# schematic.net
KiCad netlist of a schematic drawn in Altium Designer
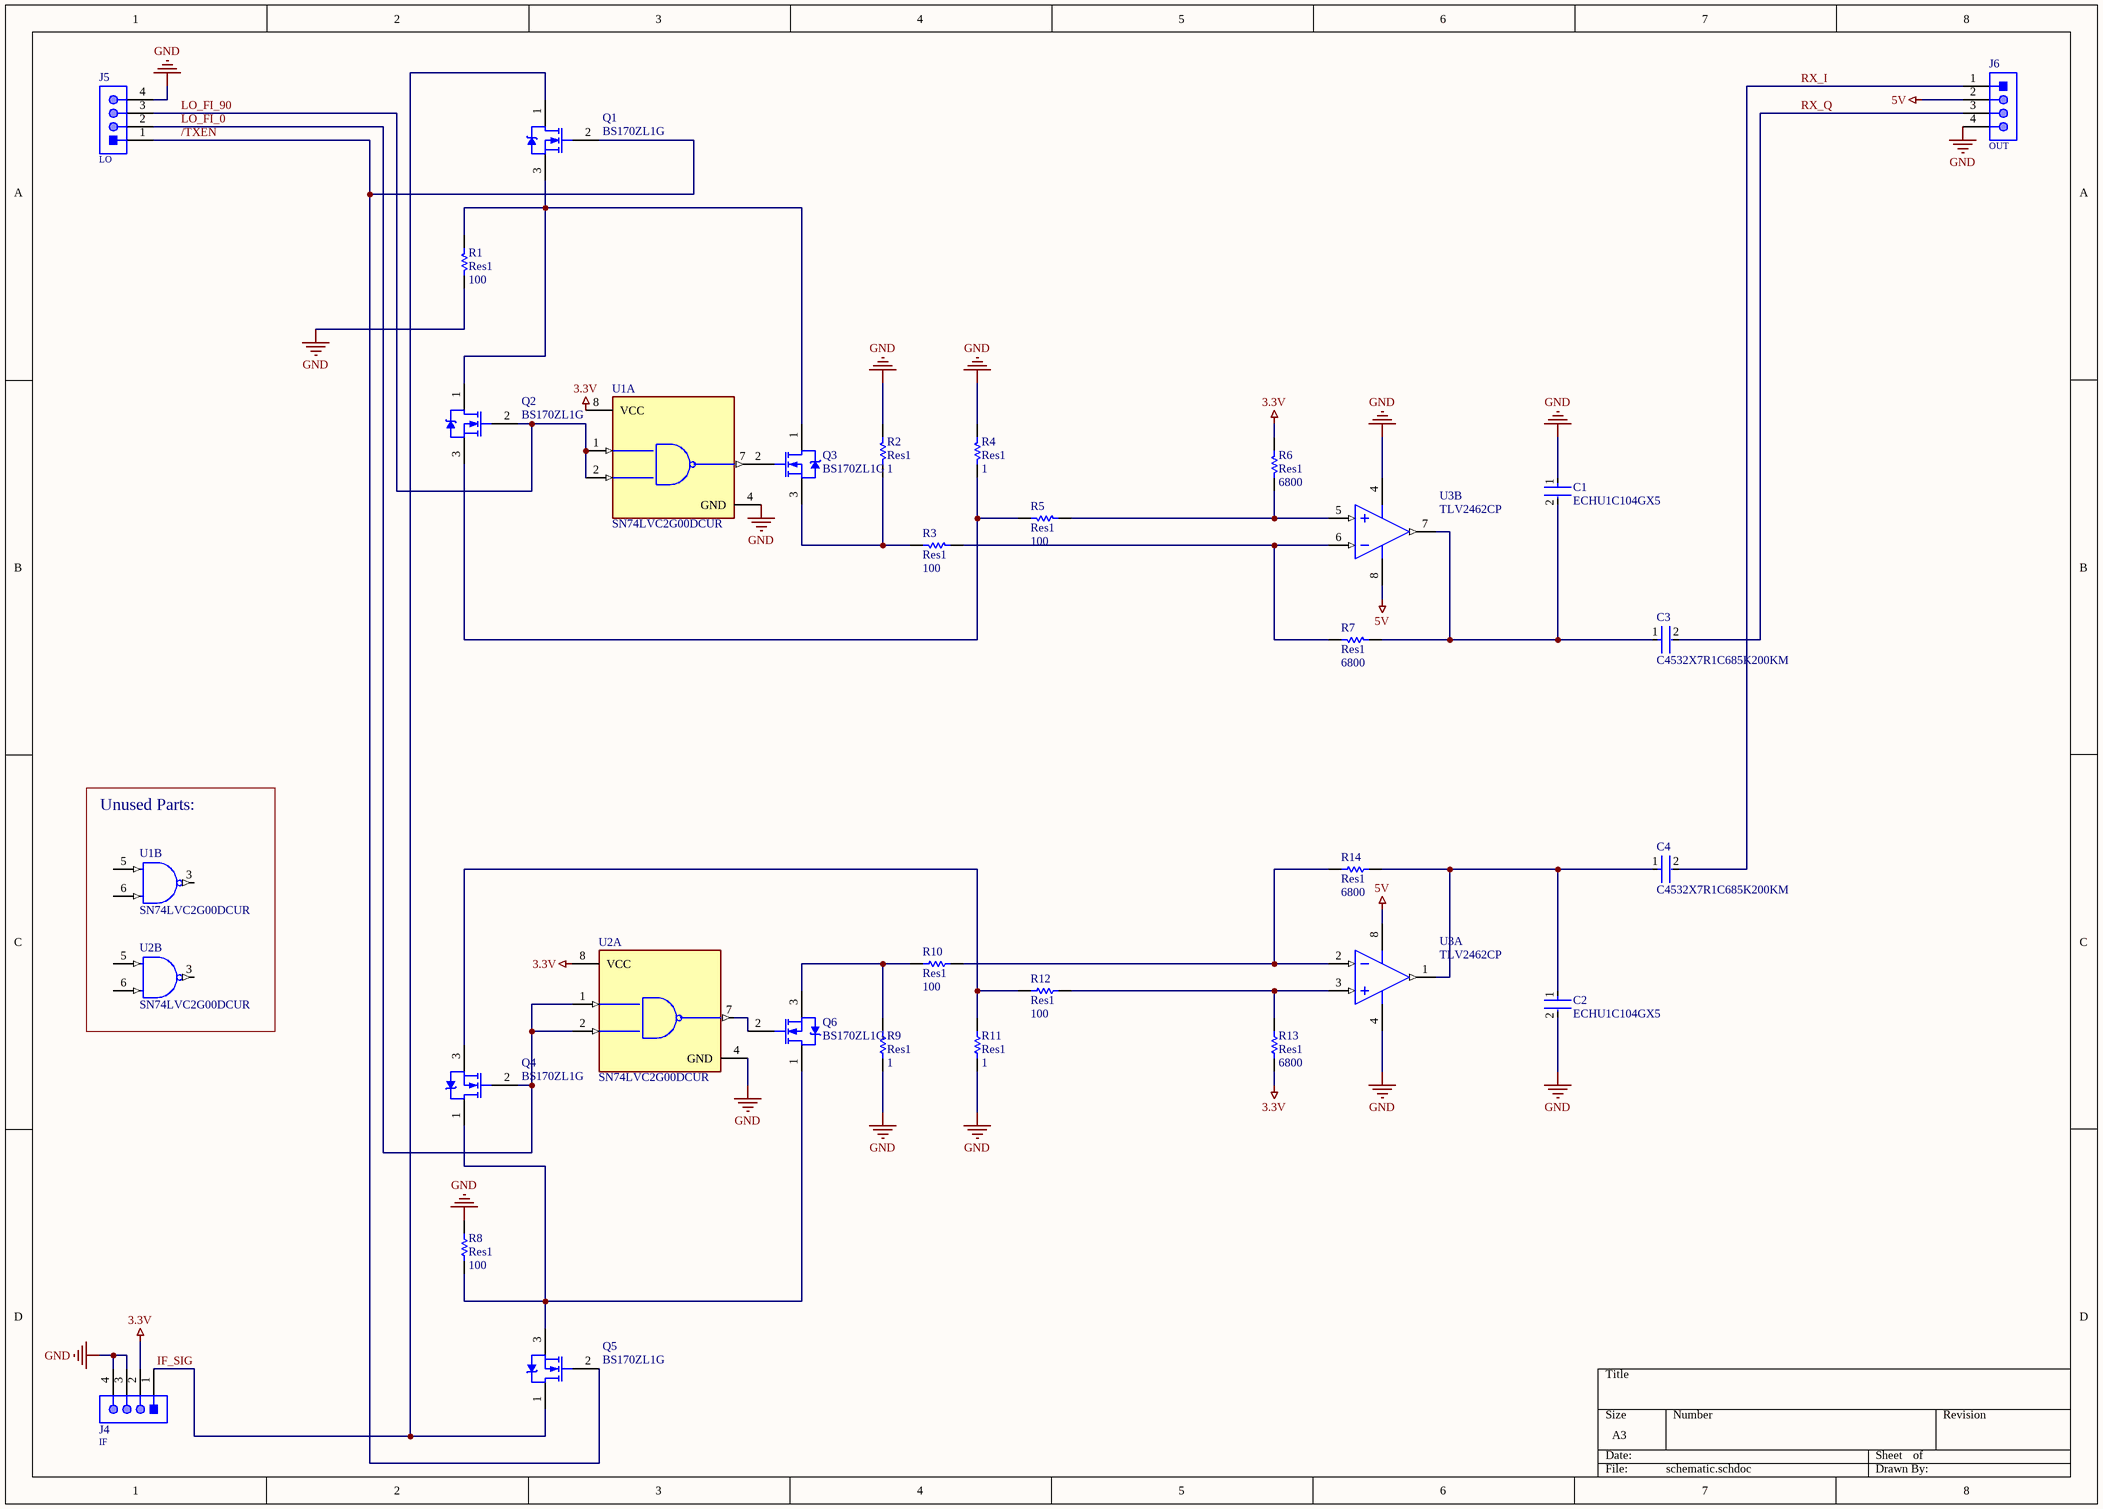
[diagram p0: schematic.schdoc]

(export (version "E")
  (design (tool "Eeschema 10.0.6"))
  (components
    (comp (ref "C1")
      (value "ECHU1C104GX5")
      (footprint "FP-ECHUG3-MFG")
      (description "CAP FILM 0.1UF 2% 16VDC 1210")
      (fields (field (name "TOLERANCE") "2%") (field (name "VOLTAGE") "16V"))
      (libsource (lib "Altium Content Vault") (part "02cd4be3c70576c341d710602a673aa"))
    )
    (comp (ref "C2")
      (value "ECHU1C104GX5")
      (footprint "FP-ECHUG3-MFG")
      (description "CAP FILM 0.1UF 2% 16VDC 1210")
      (fields (field (name "TOLERANCE") "2%") (field (name "VOLTAGE") "16V"))
      (libsource (lib "Altium Content Vault") (part "02cd4be3c70576c341d710602a673aa"))
    )
    (comp (ref "C3")
      (value "C4532X7R1C685K200KM")
      (footprint "FP-C4532-200-0_4-IPC_B")
      (description "Multilayer Ceramic Capacitors 6.8uF ±10% 16V X7R SMD 1812")
      (fields (field (name "TOLERANCE") "10%"))
      (libsource (lib "Altium Content Vault") (part "02cd4be3c70576c341d710602a673aa"))
    )
    (comp (ref "C4")
      (value "C4532X7R1C685K200KM")
      (footprint "FP-C4532-200-0_4-IPC_B")
      (description "Multilayer Ceramic Capacitors 6.8uF ±10% 16V X7R SMD 1812")
      (fields (field (name "TOLERANCE") "10%"))
      (libsource (lib "Altium Content Vault") (part "02cd4be3c70576c341d710602a673aa"))
    )
    (comp (ref "J4")
      (value "IF")
      (footprint "61300411121")
      (description "THT Vertical Pin Header WR-PHD, Pitch 2.54 mm, Single Row, 4 pins")
      (fields
        (field (name "MANUFACTURER") "Wurth Elektronik")
        (field (name "PART NUMBER") "61300411121")
        (field (name "PUBLISHER") "WurthElektronik")
      )
      (libsource (lib "Altium Content Vault") (part "WE-CN-1P-M-R4"))
    )
    (comp (ref "J5")
      (value "LO")
      (footprint "61300411121")
      (description "THT Vertical Pin Header WR-PHD, Pitch 2.54 mm, Single Row, 4 pins")
      (fields
        (field (name "MANUFACTURER") "Wurth Elektronik")
        (field (name "PART NUMBER") "61300411121")
        (field (name "PUBLISHER") "WurthElektronik")
      )
      (libsource (lib "") (part "WE-CN-1P-M-R4_2"))
    )
    (comp (ref "J6")
      (value "OUT")
      (footprint "61300411121")
      (description "THT Vertical Pin Header WR-PHD, Pitch 2.54 mm, Single Row, 4 pins")
      (fields
        (field (name "MANUFACTURER") "Wurth Elektronik")
        (field (name "PART NUMBER") "61300411121")
        (field (name "PUBLISHER") "WurthElektronik")
      )
      (libsource (lib "") (part "WE-CN-1P-M-R4_1"))
    )
    (comp (ref "Q1")
      (value "BS170ZL1G")
      (footprint "ONSC-TO-92-3-29-11_AM_BL")
      (description "Small Signal MOSFET, 500 mA, 60 V, N-Channel, 3-Pin TO-92, Pb-Free, Tape and Reel")
      (fields (field (name "MANUFACTURER") "On Semiconductor"))
      (libsource (lib "Altium Content Vault") (part "ONSC-NMOS-D1G2S3-3"))
    )
    (comp (ref "Q2")
      (value "BS170ZL1G")
      (footprint "ONSC-TO-92-3-29-11_AM_BL")
      (description "Small Signal MOSFET, 500 mA, 60 V, N-Channel, 3-Pin TO-92, Pb-Free, Tape and Reel")
      (fields (field (name "MANUFACTURER") "On Semiconductor"))
      (libsource (lib "Altium Content Vault") (part "ONSC-NMOS-D1G2S3-3"))
    )
    (comp (ref "Q3")
      (value "BS170ZL1G")
      (footprint "ONSC-TO-92-3-29-11_AM_BL")
      (description "Small Signal MOSFET, 500 mA, 60 V, N-Channel, 3-Pin TO-92, Pb-Free, Tape and Reel")
      (fields (field (name "MANUFACTURER") "On Semiconductor"))
      (libsource (lib "Altium Content Vault") (part "ONSC-NMOS-D1G2S3-3"))
    )
    (comp (ref "Q4")
      (value "BS170ZL1G")
      (footprint "ONSC-TO-92-3-29-11_AM_BL")
      (description "Small Signal MOSFET, 500 mA, 60 V, N-Channel, 3-Pin TO-92, Pb-Free, Tape and Reel")
      (fields (field (name "MANUFACTURER") "On Semiconductor"))
      (libsource (lib "Altium Content Vault") (part "ONSC-NMOS-D1G2S3-3"))
    )
    (comp (ref "Q5")
      (value "BS170ZL1G")
      (footprint "ONSC-TO-92-3-29-11_AM_BL")
      (description "Small Signal MOSFET, 500 mA, 60 V, N-Channel, 3-Pin TO-92, Pb-Free, Tape and Reel")
      (fields (field (name "MANUFACTURER") "On Semiconductor"))
      (libsource (lib "Altium Content Vault") (part "ONSC-NMOS-D1G2S3-3"))
    )
    (comp (ref "Q6")
      (value "BS170ZL1G")
      (footprint "ONSC-TO-92-3-29-11_AM_BL")
      (description "Small Signal MOSFET, 500 mA, 60 V, N-Channel, 3-Pin TO-92, Pb-Free, Tape and Reel")
      (fields (field (name "MANUFACTURER") "On Semiconductor"))
      (libsource (lib "Altium Content Vault") (part "ONSC-NMOS-D1G2S3-3"))
    )
    (comp (ref "R1")
      (value "Res1")
      (footprint "RAD-0.1")
      (description "Resistor")
      (fields (field (name "ALTIUM_VALUE") "100") (field (name "PUBLISHER") "Altium Limited"))
      (libsource (lib "Miscellaneous Devices") (part "Res1"))
    )
    (comp (ref "R2")
      (value "Res1")
      (footprint "RAD-0.1")
      (description "Resistor")
      (fields (field (name "ALTIUM_VALUE") "1") (field (name "PUBLISHER") "Altium Limited"))
      (libsource (lib "Miscellaneous Devices") (part "Res1"))
    )
    (comp (ref "R3")
      (value "Res1")
      (footprint "RAD-0.1")
      (description "Resistor")
      (fields (field (name "ALTIUM_VALUE") "100") (field (name "PUBLISHER") "Altium Limited"))
      (libsource (lib "Miscellaneous Devices") (part "Res1"))
    )
    (comp (ref "R4")
      (value "Res1")
      (footprint "RAD-0.1")
      (description "Resistor")
      (fields (field (name "ALTIUM_VALUE") "1") (field (name "PUBLISHER") "Altium Limited"))
      (libsource (lib "Miscellaneous Devices") (part "Res1"))
    )
    (comp (ref "R5")
      (value "Res1")
      (footprint "RAD-0.1")
      (description "Resistor")
      (fields (field (name "ALTIUM_VALUE") "100") (field (name "PUBLISHER") "Altium Limited"))
      (libsource (lib "Miscellaneous Devices") (part "Res1"))
    )
    (comp (ref "R6")
      (value "Res1")
      (footprint "RAD-0.1")
      (description "Resistor")
      (fields (field (name "ALTIUM_VALUE") "6800") (field (name "PUBLISHER") "Altium Limited"))
      (libsource (lib "Miscellaneous Devices") (part "Res1"))
    )
    (comp (ref "R7")
      (value "Res1")
      (footprint "RAD-0.1")
      (description "Resistor")
      (fields (field (name "ALTIUM_VALUE") "6800") (field (name "PUBLISHER") "Altium Limited"))
      (libsource (lib "Miscellaneous Devices") (part "Res1"))
    )
    (comp (ref "R8")
      (value "Res1")
      (footprint "RAD-0.1")
      (description "Resistor")
      (fields (field (name "ALTIUM_VALUE") "100") (field (name "PUBLISHER") "Altium Limited"))
      (libsource (lib "Miscellaneous Devices") (part "Res1"))
    )
    (comp (ref "R9")
      (value "Res1")
      (footprint "RAD-0.1")
      (description "Resistor")
      (fields (field (name "ALTIUM_VALUE") "1") (field (name "PUBLISHER") "Altium Limited"))
      (libsource (lib "Miscellaneous Devices") (part "Res1"))
    )
    (comp (ref "R10")
      (value "Res1")
      (footprint "RAD-0.1")
      (description "Resistor")
      (fields (field (name "ALTIUM_VALUE") "100") (field (name "PUBLISHER") "Altium Limited"))
      (libsource (lib "Miscellaneous Devices") (part "Res1"))
    )
    (comp (ref "R11")
      (value "Res1")
      (footprint "RAD-0.1")
      (description "Resistor")
      (fields (field (name "ALTIUM_VALUE") "1") (field (name "PUBLISHER") "Altium Limited"))
      (libsource (lib "Miscellaneous Devices") (part "Res1"))
    )
    (comp (ref "R12")
      (value "Res1")
      (footprint "RAD-0.1")
      (description "Resistor")
      (fields (field (name "ALTIUM_VALUE") "100") (field (name "PUBLISHER") "Altium Limited"))
      (libsource (lib "Miscellaneous Devices") (part "Res1"))
    )
    (comp (ref "R13")
      (value "Res1")
      (footprint "RAD-0.1")
      (description "Resistor")
      (fields (field (name "ALTIUM_VALUE") "6800") (field (name "PUBLISHER") "Altium Limited"))
      (libsource (lib "Miscellaneous Devices") (part "Res1"))
    )
    (comp (ref "R14")
      (value "Res1")
      (footprint "RAD-0.1")
      (description "Resistor")
      (fields (field (name "ALTIUM_VALUE") "6800") (field (name "PUBLISHER") "Altium Limited"))
      (libsource (lib "Miscellaneous Devices") (part "Res1"))
    )
    (comp (ref "U1")
      (value "SN74LVC2G00DCUR")
      (footprint "FP-DCU0008A-IPC_C")
      (description "IC GATE NAND 2CH 2-INP US8")
      (libsource (lib "Altium Content Vault") (part "c5330445c9508bb612cd4c79c3c98cb"))
    )
    (comp (ref "U2")
      (value "SN74LVC2G00DCUR")
      (footprint "FP-DCU0008A-IPC_C")
      (description "IC GATE NAND 2CH 2-INP US8")
      (libsource (lib "Altium Content Vault") (part "c5330445c9508bb612cd4c79c3c98cb"))
    )
    (comp (ref "U3")
      (value "TLV2462CP")
      (footprint "P0008A")
      (fields (field (name "MANUFACTURER") "Texas Instruments"))
      (libsource (lib "Altium Content Vault") (part "TI-TLV2462-8"))
    )
  )
  (nets
    (net (code "2") (name "/IF_SIG") (class "Default")
      (node (ref "J4") (pin "1") (pinfunction "1_1") (pintype "passive"))
      (node (ref "Q1") (pin "1") (pinfunction "D_1") (pintype "passive"))
      (node (ref "Q5") (pin "1") (pinfunction "D_1") (pintype "passive"))
    )
    (net (code "3") (name "/LO_FI_0") (class "Default")
      (node (ref "J5") (pin "2") (pinfunction "2_2") (pintype "passive"))
      (node (ref "Q4") (pin "2") (pinfunction "G_2") (pintype "passive"))
      (node (ref "U2") (pin "1") (pinfunction "1A_1") (pintype "input"))
      (node (ref "U2") (pin "2") (pinfunction "1B_2") (pintype "input"))
    )
    (net (code "4") (name "/LO_FI_90") (class "Default")
      (node (ref "J5") (pin "3") (pinfunction "3_3") (pintype "passive"))
      (node (ref "Q2") (pin "2") (pinfunction "G_2") (pintype "passive"))
      (node (ref "U1") (pin "1") (pinfunction "1A_1") (pintype "input"))
      (node (ref "U1") (pin "2") (pinfunction "1B_2") (pintype "input"))
    )
    (net (code "5") (name "/RX_I") (class "Default")
      (node (ref "C4") (pin "2") (pinfunction "2_2") (pintype "passive"))
      (node (ref "J6") (pin "1") (pinfunction "1_1") (pintype "passive"))
    )
    (net (code "6") (name "/RX_Q") (class "Default")
      (node (ref "C3") (pin "2") (pinfunction "2_2") (pintype "passive"))
      (node (ref "J6") (pin "3") (pinfunction "3_3") (pintype "passive"))
    )
    (net (code "7") (name "/{slash}TXEN") (class "Default")
      (node (ref "J5") (pin "1") (pinfunction "1_1") (pintype "passive"))
      (node (ref "Q1") (pin "2") (pinfunction "G_2") (pintype "passive"))
      (node (ref "Q5") (pin "2") (pinfunction "G_2") (pintype "passive"))
    )
    (net (code "8") (name "3.3V") (class "Default")
      (node (ref "J4") (pin "2") (pinfunction "2_2") (pintype "passive"))
      (node (ref "R13") (pin "1") (pinfunction "1_1") (pintype "passive"))
      (node (ref "R6") (pin "1") (pinfunction "1_1") (pintype "passive"))
      (node (ref "U1") (pin "8") (pinfunction "VCC_8") (pintype "power_in"))
      (node (ref "U2") (pin "8") (pinfunction "VCC_8") (pintype "power_in"))
    )
    (net (code "9") (name "5V") (class "Default")
      (node (ref "J6") (pin "2") (pinfunction "2_2") (pintype "passive"))
      (node (ref "U3") (pin "8") (pinfunction "VDD+_8") (pintype "power_in"))
    )
    (net (code "10") (name "GND") (class "Default")
      (node (ref "C1") (pin "1") (pinfunction "1_1") (pintype "passive"))
      (node (ref "C2") (pin "2") (pinfunction "2_2") (pintype "passive"))
      (node (ref "J4") (pin "3") (pinfunction "3_3") (pintype "passive"))
      (node (ref "J4") (pin "4") (pinfunction "4_4") (pintype "passive"))
      (node (ref "J5") (pin "4") (pinfunction "4_4") (pintype "passive"))
      (node (ref "J6") (pin "4") (pinfunction "4_4") (pintype "passive"))
      (node (ref "R1") (pin "2") (pinfunction "2_2") (pintype "passive"))
      (node (ref "R11") (pin "1") (pinfunction "1_1") (pintype "passive"))
      (node (ref "R2") (pin "1") (pinfunction "1_1") (pintype "passive"))
      (node (ref "R4") (pin "1") (pinfunction "1_1") (pintype "passive"))
      (node (ref "R8") (pin "2") (pinfunction "2_2") (pintype "passive"))
      (node (ref "R9") (pin "1") (pinfunction "1_1") (pintype "passive"))
      (node (ref "U1") (pin "4") (pinfunction "GND_4") (pintype "power_in"))
      (node (ref "U2") (pin "4") (pinfunction "GND_4") (pintype "power_in"))
      (node (ref "U3") (pin "4") (pinfunction "GND_4") (pintype "power_in"))
    )
    (net (code "11") (name "Net-(Q1-S)") (class "Default")
      (node (ref "Q1") (pin "3") (pinfunction "S_3") (pintype "passive"))
      (node (ref "Q2") (pin "1") (pinfunction "D_1") (pintype "passive"))
      (node (ref "Q3") (pin "1") (pinfunction "D_1") (pintype "passive"))
      (node (ref "R1") (pin "1") (pinfunction "1_1") (pintype "passive"))
    )
    (net (code "12") (name "Net-(Q2-S)") (class "Default")
      (node (ref "Q2") (pin "3") (pinfunction "S_3") (pintype "passive"))
      (node (ref "R4") (pin "2") (pinfunction "2_2") (pintype "passive"))
      (node (ref "R5") (pin "1") (pinfunction "1_1") (pintype "passive"))
    )
    (net (code "13") (name "Net-(Q3-G)") (class "Default")
      (node (ref "Q3") (pin "2") (pinfunction "G_2") (pintype "passive"))
      (node (ref "U1") (pin "7") (pinfunction "1Y_7") (pintype "output"))
    )
    (net (code "14") (name "Net-(Q3-S)") (class "Default")
      (node (ref "Q3") (pin "3") (pinfunction "S_3") (pintype "passive"))
      (node (ref "R2") (pin "2") (pinfunction "2_2") (pintype "passive"))
      (node (ref "R3") (pin "1") (pinfunction "1_1") (pintype "passive"))
    )
    (net (code "15") (name "Net-(Q4-D)") (class "Default")
      (node (ref "Q4") (pin "1") (pinfunction "D_1") (pintype "passive"))
      (node (ref "Q5") (pin "3") (pinfunction "S_3") (pintype "passive"))
      (node (ref "Q6") (pin "1") (pinfunction "D_1") (pintype "passive"))
      (node (ref "R8") (pin "1") (pinfunction "1_1") (pintype "passive"))
    )
    (net (code "16") (name "Net-(Q4-S)") (class "Default")
      (node (ref "Q4") (pin "3") (pinfunction "S_3") (pintype "passive"))
      (node (ref "R11") (pin "2") (pinfunction "2_2") (pintype "passive"))
      (node (ref "R12") (pin "1") (pinfunction "1_1") (pintype "passive"))
    )
    (net (code "17") (name "Net-(Q6-G)") (class "Default")
      (node (ref "Q6") (pin "2") (pinfunction "G_2") (pintype "passive"))
      (node (ref "U2") (pin "7") (pinfunction "1Y_7") (pintype "output"))
    )
    (net (code "18") (name "Net-(Q6-S)") (class "Default")
      (node (ref "Q6") (pin "3") (pinfunction "S_3") (pintype "passive"))
      (node (ref "R10") (pin "1") (pinfunction "1_1") (pintype "passive"))
      (node (ref "R9") (pin "2") (pinfunction "2_2") (pintype "passive"))
    )
    (net (code "19") (name "Net-(U3A-IN1+)") (class "Default")
      (node (ref "R12") (pin "2") (pinfunction "2_2") (pintype "passive"))
      (node (ref "R13") (pin "2") (pinfunction "2_2") (pintype "passive"))
      (node (ref "U3") (pin "3") (pinfunction "IN1+_3") (pintype "input"))
    )
    (net (code "20") (name "Net-(U3A-IN1-)") (class "Default")
      (node (ref "R10") (pin "2") (pinfunction "2_2") (pintype "passive"))
      (node (ref "R14") (pin "1") (pinfunction "1_1") (pintype "passive"))
      (node (ref "U3") (pin "2") (pinfunction "IN1-_2") (pintype "input"))
    )
    (net (code "21") (name "Net-(U3A-OUT1)") (class "Default")
      (node (ref "C2") (pin "1") (pinfunction "1_1") (pintype "passive"))
      (node (ref "C4") (pin "1") (pinfunction "1_1") (pintype "passive"))
      (node (ref "R14") (pin "2") (pinfunction "2_2") (pintype "passive"))
      (node (ref "U3") (pin "1") (pinfunction "OUT1_1") (pintype "output"))
    )
    (net (code "22") (name "Net-(U3B-IN2+)") (class "Default")
      (node (ref "R5") (pin "2") (pinfunction "2_2") (pintype "passive"))
      (node (ref "R6") (pin "2") (pinfunction "2_2") (pintype "passive"))
      (node (ref "U3") (pin "5") (pinfunction "IN2+_5") (pintype "input"))
    )
    (net (code "23") (name "Net-(U3B-IN2-)") (class "Default")
      (node (ref "R3") (pin "2") (pinfunction "2_2") (pintype "passive"))
      (node (ref "R7") (pin "1") (pinfunction "1_1") (pintype "passive"))
      (node (ref "U3") (pin "6") (pinfunction "IN2-_6") (pintype "input"))
    )
    (net (code "24") (name "Net-(U3B-OUT2)") (class "Default")
      (node (ref "C1") (pin "2") (pinfunction "2_2") (pintype "passive"))
      (node (ref "C3") (pin "1") (pinfunction "1_1") (pintype "passive"))
      (node (ref "R7") (pin "2") (pinfunction "2_2") (pintype "passive"))
      (node (ref "U3") (pin "7") (pinfunction "OUT2_7") (pintype "output"))
    )
    (net (code "25") (name "unconnected-(U1B-2A-Pad5)") (class "Default")
      (node (ref "U1") (pin "5") (pinfunction "2A_5") (pintype "input"))
    )
    (net (code "26") (name "unconnected-(U1B-2B-Pad6)") (class "Default")
      (node (ref "U1") (pin "6") (pinfunction "2B_6") (pintype "input"))
    )
    (net (code "27") (name "unconnected-(U1B-2Y-Pad3)") (class "Default")
      (node (ref "U1") (pin "3") (pinfunction "2Y_3") (pintype "output"))
    )
    (net (code "28") (name "unconnected-(U2B-2A-Pad5)") (class "Default")
      (node (ref "U2") (pin "5") (pinfunction "2A_5") (pintype "input"))
    )
    (net (code "29") (name "unconnected-(U2B-2B-Pad6)") (class "Default")
      (node (ref "U2") (pin "6") (pinfunction "2B_6") (pintype "input"))
    )
    (net (code "30") (name "unconnected-(U2B-2Y-Pad3)") (class "Default")
      (node (ref "U2") (pin "3") (pinfunction "2Y_3") (pintype "output"))
    )
  )
)
